# main.net
KiCad netlist of a schematic drawn in EAGLE
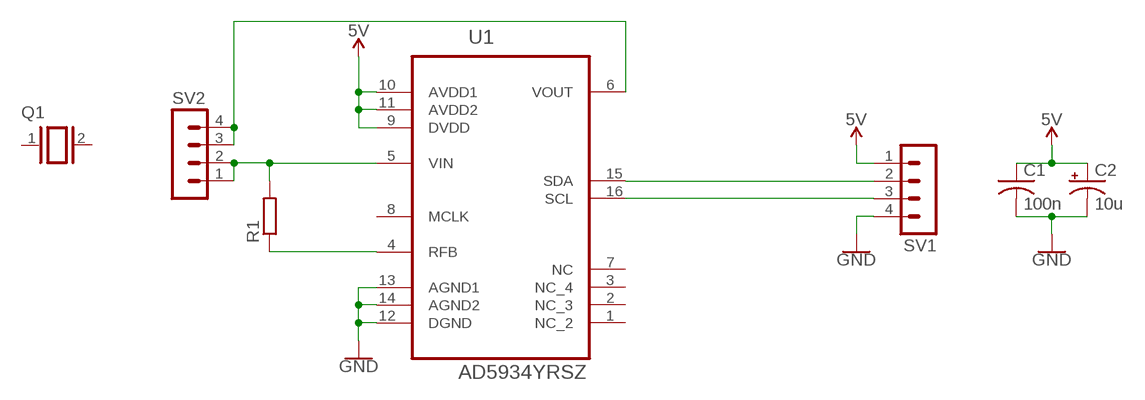
[diagram p0: schematic, sheet 1]

(export (version "E")
  (design (tool "Eeschema 10.0.6"))
  (components
    (comp (ref "C1")
      (value "100n")
      (footprint "eagle-import:C025-025X050")
      (libsource (lib "eagle-import") (part "C-US025-025X050"))
    )
    (comp (ref "C2")
      (value "10u")
      (footprint "eagle-import:E2-5")
      (libsource (lib "eagle-import") (part "CPOL-USE2-5"))
    )
    (comp (ref "Q1")
      (value "XTAL/S")
      (footprint "eagle-import:QS")
      (libsource (lib "eagle-import") (part "XTAL/S"))
    )
    (comp (ref "R1")
      (value "R0204/7")
      (footprint "eagle-import:0204_7")
      (libsource (lib "eagle-import") (part "R0204/7"))
    )
    (comp (ref "SV1")
      (value "MA04-1")
      (footprint "eagle-import:MA04-1")
      (libsource (lib "eagle-import") (part "MA04-1"))
    )
    (comp (ref "SV2")
      (value "MA04-1")
      (footprint "eagle-import:MA04-1")
      (libsource (lib "eagle-import") (part "MA04-1"))
    )
    (comp (ref "U1")
      (value "AD5934YRSZ")
      (footprint "eagle-import:SOP65P780X200-16N")
      (libsource (lib "eagle-import") (part "AD5934YRSZ"))
    )
  )
  (nets
    (net (code "1") (name "5V") (class "Default")
      (node (ref "C1") (pin "1") (pinfunction "1_1") (pintype "passive"))
      (node (ref "C2") (pin "+") (pinfunction "+_+") (pintype "passive"))
      (node (ref "SV1") (pin "1") (pinfunction "1_1") (pintype "passive"))
      (node (ref "U1") (pin "10") (pinfunction "AVDD1_10") (pintype "passive"))
      (node (ref "U1") (pin "11") (pinfunction "AVDD2_11") (pintype "passive"))
      (node (ref "U1") (pin "9") (pinfunction "DVDD_9") (pintype "passive"))
    )
    (net (code "2") (name "GND") (class "Default")
      (node (ref "C1") (pin "2") (pinfunction "2_2") (pintype "passive"))
      (node (ref "C2") (pin "-") (pinfunction "-_-") (pintype "passive"))
      (node (ref "SV1") (pin "4") (pinfunction "4_4") (pintype "passive"))
      (node (ref "U1") (pin "12") (pinfunction "DGND_12") (pintype "passive"))
      (node (ref "U1") (pin "13") (pinfunction "AGND1_13") (pintype "passive"))
      (node (ref "U1") (pin "14") (pinfunction "AGND2_14") (pintype "passive"))
    )
    (net (code "3") (name "Net-(U1-RFB)") (class "Default")
      (node (ref "R1") (pin "1") (pinfunction "1_1") (pintype "passive"))
      (node (ref "U1") (pin "4") (pinfunction "RFB_4") (pintype "passive"))
    )
    (net (code "4") (name "Net-(U1-SCL)") (class "Default")
      (node (ref "SV1") (pin "3") (pinfunction "3_3") (pintype "passive"))
      (node (ref "U1") (pin "16") (pinfunction "SCL_16") (pintype "passive"))
    )
    (net (code "5") (name "Net-(U1-SDA)") (class "Default")
      (node (ref "SV1") (pin "2") (pinfunction "2_2") (pintype "passive"))
      (node (ref "U1") (pin "15") (pinfunction "SDA_15") (pintype "passive"))
    )
    (net (code "6") (name "Net-(U1-VIN)") (class "Default")
      (node (ref "R1") (pin "2") (pinfunction "2_2") (pintype "passive"))
      (node (ref "SV2") (pin "1") (pinfunction "1_1") (pintype "passive"))
      (node (ref "SV2") (pin "2") (pinfunction "2_2") (pintype "passive"))
      (node (ref "U1") (pin "5") (pinfunction "VIN_5") (pintype "passive"))
    )
    (net (code "7") (name "Net-(U1-VOUT)") (class "Default")
      (node (ref "SV2") (pin "3") (pinfunction "3_3") (pintype "passive"))
      (node (ref "SV2") (pin "4") (pinfunction "4_4") (pintype "passive"))
      (node (ref "U1") (pin "6") (pinfunction "VOUT_6") (pintype "passive"))
    )
    (net (code "8") (name "unconnected-(Q1-Pad1)") (class "Default")
      (node (ref "Q1") (pin "1") (pinfunction "1_1") (pintype "passive"))
    )
    (net (code "9") (name "unconnected-(Q1-Pad2)") (class "Default")
      (node (ref "Q1") (pin "2") (pinfunction "2_2") (pintype "passive"))
    )
    (net (code "10") (name "unconnected-(U1-MCLK-Pad8)") (class "Default")
      (node (ref "U1") (pin "8") (pinfunction "MCLK_8") (pintype "passive"))
    )
    (net (code "11") (name "unconnected-(U1-NC-Pad7)") (class "Default")
      (node (ref "U1") (pin "7") (pinfunction "NC_7") (pintype "passive"))
    )
    (net (code "12") (name "unconnected-(U1-NC_2-Pad1)") (class "Default")
      (node (ref "U1") (pin "1") (pinfunction "NC_2_1") (pintype "passive"))
    )
    (net (code "13") (name "unconnected-(U1-NC_3-Pad2)") (class "Default")
      (node (ref "U1") (pin "2") (pinfunction "NC_3_2") (pintype "passive"))
    )
    (net (code "14") (name "unconnected-(U1-NC_4-Pad3)") (class "Default")
      (node (ref "U1") (pin "3") (pinfunction "NC_4_3") (pintype "passive"))
    )
  )
)
